# ELASORB01.net
KiCad netlist of a schematic drawn in EAGLE
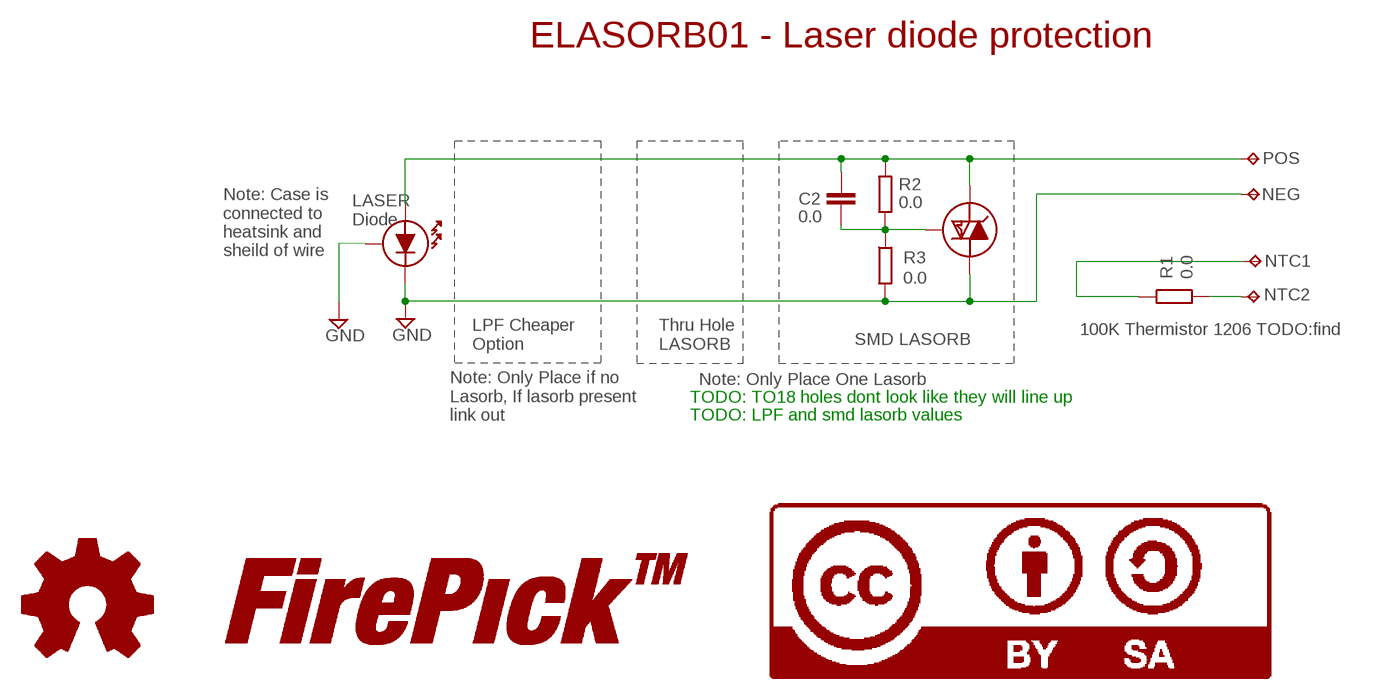
[diagram p0: schematic, sheet 1]

(export (version "E")
  (design (tool "Eeschema 10.0.6"))
  (components
    (comp (ref "C2")
      (value "0.0")
      (footprint "eagle-import:C0603K")
      (libsource (lib "eagle-import") (part "C-EUC0603K"))
    )
    (comp (ref "D1")
      (value "LASER_DIODE")
      (footprint "eagle-import:TO18")
      (libsource (lib "eagle-import") (part "LASER_DIODE"))
    )
    (comp (ref "LOGO1")
      (value "LOGO-CC-BY-SASMALL")
      (footprint "eagle-import:LOGO-CC-BY-SA-SMALL")
      (libsource (lib "eagle-import") (part "LOGO-CC-BY-SASMALL"))
    )
    (comp (ref "LOGO2")
      (value "LOGO-FIREPICKSMALL")
      (footprint "eagle-import:LOGO-FIREPICK-SMALL")
      (libsource (lib "eagle-import") (part "LOGO-FIREPICKSMALL"))
    )
    (comp (ref "LOGO3")
      (value "LOGO-OSHWSMALL")
      (footprint "eagle-import:LOGO-OSHW-SMALL")
      (libsource (lib "eagle-import") (part "LOGO-OSHWSMALL"))
    )
    (comp (ref "NEG")
      (value "TPTP16R")
      (footprint "eagle-import:TP16R")
      (libsource (lib "eagle-import") (part "TPTP16R"))
    )
    (comp (ref "NTC1")
      (value "TPTP16R")
      (footprint "eagle-import:TP16R")
      (libsource (lib "eagle-import") (part "TPTP16R"))
    )
    (comp (ref "NTC2")
      (value "TPTP16R")
      (footprint "eagle-import:TP16R")
      (libsource (lib "eagle-import") (part "TPTP16R"))
    )
    (comp (ref "POS")
      (value "TPTP16R")
      (footprint "eagle-import:TP16R")
      (libsource (lib "eagle-import") (part "TPTP16R"))
    )
    (comp (ref "R1")
      (value "0.0")
      (footprint "eagle-import:R1206")
      (libsource (lib "eagle-import") (part "R-EU_R1206"))
    )
    (comp (ref "R2")
      (value "0.0")
      (footprint "eagle-import:R0603")
      (libsource (lib "eagle-import") (part "R-EU_R0603"))
    )
    (comp (ref "R3")
      (value "0.0")
      (footprint "eagle-import:R0603")
      (libsource (lib "eagle-import") (part "R-EU_R0603"))
    )
    (comp (ref "U2")
      (value "LASORB_SMD")
      (footprint "eagle-import:TSOP-6")
      (libsource (lib "eagle-import") (part "LASORB_SMD"))
    )
  )
  (nets
    (net (code "1") (name "GND") (class "Default")
      (node (ref "D1") (pin "2") (pinfunction "CASE_2") (pintype "passive"))
      (node (ref "D1") (pin "3") (pinfunction "K_3") (pintype "passive"))
      (node (ref "NEG") (pin "TP") (pinfunction "TP_TP") (pintype "input"))
      (node (ref "R3") (pin "2") (pinfunction "2_2") (pintype "passive"))
      (node (ref "U2") (pin "P$4") (pinfunction "LDK_P$4") (pintype "passive"))
    )
    (net (code "2") (name "Net-(D1-A)") (class "Default")
      (node (ref "C2") (pin "1") (pinfunction "1_1") (pintype "passive"))
      (node (ref "D1") (pin "1") (pinfunction "A_1") (pintype "passive"))
      (node (ref "POS") (pin "TP") (pinfunction "TP_TP") (pintype "input"))
      (node (ref "R2") (pin "2") (pinfunction "2_2") (pintype "passive"))
      (node (ref "U2") (pin "P$1") (pinfunction "LDA_P$1") (pintype "passive"))
      (node (ref "U2") (pin "P$2") (pinfunction "LDA_P$2") (pintype "passive"))
      (node (ref "U2") (pin "P$5") (pinfunction "LDA_P$5") (pintype "passive"))
      (node (ref "U2") (pin "P$6") (pinfunction "LDA_P$6") (pintype "passive"))
    )
    (net (code "3") (name "Net-(NTC1-PadTP)") (class "Default")
      (node (ref "NTC1") (pin "TP") (pinfunction "TP_TP") (pintype "input"))
      (node (ref "R1") (pin "1") (pinfunction "1_1") (pintype "passive"))
    )
    (net (code "4") (name "Net-(NTC2-PadTP)") (class "Default")
      (node (ref "NTC2") (pin "TP") (pinfunction "TP_TP") (pintype "input"))
      (node (ref "R1") (pin "2") (pinfunction "2_2") (pintype "passive"))
    )
    (net (code "5") (name "Net-(U2-3-TRIG)") (class "Default")
      (node (ref "C2") (pin "2") (pinfunction "2_2") (pintype "passive"))
      (node (ref "R2") (pin "1") (pinfunction "1_1") (pintype "passive"))
      (node (ref "R3") (pin "1") (pinfunction "1_1") (pintype "passive"))
      (node (ref "U2") (pin "P$3") (pinfunction "3-TRIG_P$3") (pintype "passive"))
    )
  )
)
